# frontbreakoutSchematic.net
KiCad netlist of a schematic drawn in Altium Designer
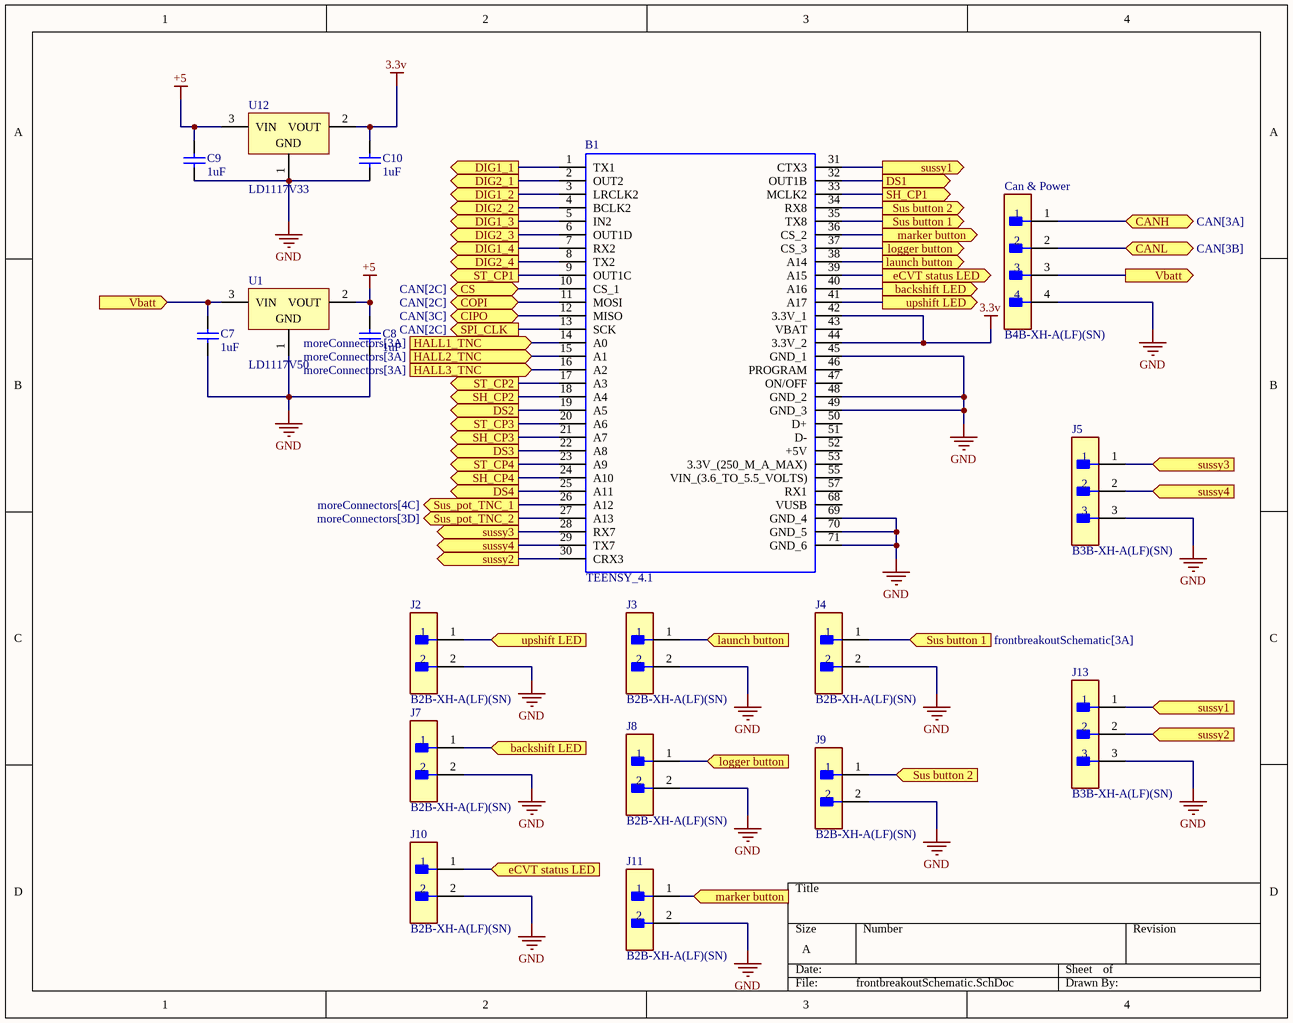
[diagram p0: frontbreakoutSchematic.SchDoc]

(export (version "E")
  (design (tool "Eeschema 10.0.6"))
  (components
    (comp (ref "B1")
      (value "TEENSY_4.1")
      (footprint "TEENSY41")
      (description "Teensy 4.1 Development Board")
      (fields (field (name "MANUFACTURER_PART_NUMBER") "TEENSY 4.1"))
      (libsource (lib "TEENSY_4.1") (part "TEENSY_4.1"))
    )
    (comp (ref "C7")
      (value "1uF")
      (footprint "CAPC2013X145X50LL20T25")
      (description "C0805C105K4PACTU")
      (fields (field (name "MANUFACTURER") "Kemet"))
      (libsource (lib "Altium Content Vault") (part "CAP"))
    )
    (comp (ref "C8")
      (value "1uF")
      (footprint "CAPC2013X145X50LL20T25")
      (description "C0805C105K4PACTU")
      (fields (field (name "MANUFACTURER") "Kemet"))
      (libsource (lib "Altium Content Vault") (part "CAP"))
    )
    (comp (ref "C9")
      (value "1uF")
      (footprint "CAPC2013X145X50LL20T25")
      (description "C0805C105K4PACTU")
      (fields (field (name "MANUFACTURER") "Kemet"))
      (libsource (lib "Altium Content Vault") (part "CAP"))
    )
    (comp (ref "C10")
      (value "1uF")
      (footprint "CAPC2013X145X50LL20T25")
      (description "C0805C105K4PACTU")
      (fields (field (name "MANUFACTURER") "Kemet"))
      (libsource (lib "Altium Content Vault") (part "CAP"))
    )
    (comp (ref "Can & Power")
      (value "B4B-XH-A(LF)(SN)")
      (footprint "FP-B4B-XH-A_LF_SN-MFG")
      (description "CONN HEADER VERT 4POS 2.5MM")
      (libsource (lib "Altium Content Vault") (part "299a8cea1bdcbc3624fe62c390fa72c"))
    )
    (comp (ref "J2")
      (value "B2B-XH-A(LF)(SN)")
      (footprint "FP-B2B-XH-A_LF_SN-MFG")
      (description "CONN HEADER VERT 2POS 2.5MM")
      (libsource (lib "Altium Content Vault") (part "3bc925449376181038e59eaffc5286c"))
    )
    (comp (ref "J3")
      (value "B2B-XH-A(LF)(SN)")
      (footprint "FP-B2B-XH-A_LF_SN-MFG")
      (description "CONN HEADER VERT 2POS 2.5MM")
      (libsource (lib "Altium Content Vault") (part "3bc925449376181038e59eaffc5286c"))
    )
    (comp (ref "J4")
      (value "B2B-XH-A(LF)(SN)")
      (footprint "FP-B2B-XH-A_LF_SN-MFG")
      (description "CONN HEADER VERT 2POS 2.5MM")
      (libsource (lib "Altium Content Vault") (part "3bc925449376181038e59eaffc5286c"))
    )
    (comp (ref "J5")
      (value "B3B-XH-A(LF)(SN)")
      (footprint "FP-B3B-XH-A_LF_SN-MFG")
      (description "CONN HEADER VERT 3POS 2.5MM")
      (libsource (lib "Altium Content Vault") (part "0d3f023dd272f625e17a2be33dea85f"))
    )
    (comp (ref "J7")
      (value "B2B-XH-A(LF)(SN)")
      (footprint "FP-B2B-XH-A_LF_SN-MFG")
      (description "CONN HEADER VERT 2POS 2.5MM")
      (libsource (lib "Altium Content Vault") (part "3bc925449376181038e59eaffc5286c"))
    )
    (comp (ref "J8")
      (value "B2B-XH-A(LF)(SN)")
      (footprint "FP-B2B-XH-A_LF_SN-MFG")
      (description "CONN HEADER VERT 2POS 2.5MM")
      (libsource (lib "Altium Content Vault") (part "3bc925449376181038e59eaffc5286c"))
    )
    (comp (ref "J9")
      (value "B2B-XH-A(LF)(SN)")
      (footprint "FP-B2B-XH-A_LF_SN-MFG")
      (description "CONN HEADER VERT 2POS 2.5MM")
      (libsource (lib "Altium Content Vault") (part "3bc925449376181038e59eaffc5286c"))
    )
    (comp (ref "J10")
      (value "B2B-XH-A(LF)(SN)")
      (footprint "FP-B2B-XH-A_LF_SN-MFG")
      (description "CONN HEADER VERT 2POS 2.5MM")
      (libsource (lib "Altium Content Vault") (part "3bc925449376181038e59eaffc5286c"))
    )
    (comp (ref "J11")
      (value "B2B-XH-A(LF)(SN)")
      (footprint "FP-B2B-XH-A_LF_SN-MFG")
      (description "CONN HEADER VERT 2POS 2.5MM")
      (libsource (lib "Altium Content Vault") (part "3bc925449376181038e59eaffc5286c"))
    )
    (comp (ref "J13")
      (value "B3B-XH-A(LF)(SN)")
      (footprint "FP-B3B-XH-A_LF_SN-MFG")
      (description "CONN HEADER VERT 3POS 2.5MM")
      (libsource (lib "Altium Content Vault") (part "0d3f023dd272f625e17a2be33dea85f"))
    )
    (comp (ref "U1")
      (value "LD1117V50")
      (footprint "TO220")
      (description "Fixed Low Drop Positive Voltage Regulator, 5V, 3-Pin TO-220")
      (libsource (lib "Altium Content Vault") (part "PM-REG-LD1117V-SIL3"))
    )
    (comp (ref "U12")
      (value "LD1117V33")
      (footprint "TO220")
      (description "Fixed Low Drop Positive Voltage Regulator, 3.3V, 3-Pin TO-220")
      (libsource (lib "Altium Content Vault") (part "PM-REG-LD1117V-SIL3"))
    )
  )
  (nets
    (net (code "1") (name "+5") (class "Default")
      (node (ref "C8") (pin "2") (pinfunction "2_2") (pintype "passive"))
      (node (ref "C9") (pin "2") (pinfunction "2_2") (pintype "passive"))
      (node (ref "U1") (pin "2") (pinfunction "VOUT_2") (pintype "power_in"))
      (node (ref "U12") (pin "3") (pinfunction "VIN_3") (pintype "power_in"))
    )
    (net (code "2") (name "/CANH") (class "Default")
      (node (ref "Can & Power") (pin "1") (pinfunction "1_1") (pintype "passive"))
    )
    (net (code "3") (name "/CANL") (class "Default")
      (node (ref "Can & Power") (pin "2") (pinfunction "2_2") (pintype "passive"))
    )
    (net (code "4") (name "/CIPO") (class "Default")
      (node (ref "B1") (pin "12") (pinfunction "MISO_12") (pintype "passive"))
    )
    (net (code "5") (name "/COPI") (class "Default")
      (node (ref "B1") (pin "11") (pinfunction "MOSI_11") (pintype "passive"))
    )
    (net (code "6") (name "/CS") (class "Default")
      (node (ref "B1") (pin "10") (pinfunction "CS_1_10") (pintype "passive"))
    )
    (net (code "7") (name "/DIG1_1") (class "Default")
      (node (ref "B1") (pin "1") (pinfunction "TX1_1") (pintype "passive"))
    )
    (net (code "8") (name "/DIG1_2") (class "Default")
      (node (ref "B1") (pin "3") (pinfunction "LRCLK2_3") (pintype "passive"))
    )
    (net (code "9") (name "/DIG1_3") (class "Default")
      (node (ref "B1") (pin "5") (pinfunction "IN2_5") (pintype "passive"))
    )
    (net (code "10") (name "/DIG1_4") (class "Default")
      (node (ref "B1") (pin "7") (pinfunction "RX2_7") (pintype "passive"))
    )
    (net (code "11") (name "/DIG2_1") (class "Default")
      (node (ref "B1") (pin "2") (pinfunction "OUT2_2") (pintype "passive"))
    )
    (net (code "12") (name "/DIG2_2") (class "Default")
      (node (ref "B1") (pin "4") (pinfunction "BCLK2_4") (pintype "passive"))
    )
    (net (code "13") (name "/DIG2_3") (class "Default")
      (node (ref "B1") (pin "6") (pinfunction "OUT1D_6") (pintype "passive"))
    )
    (net (code "14") (name "/DIG2_4") (class "Default")
      (node (ref "B1") (pin "8") (pinfunction "TX2_8") (pintype "passive"))
    )
    (net (code "15") (name "/DS1") (class "Default")
      (node (ref "B1") (pin "32") (pinfunction "OUT1B_32") (pintype "passive"))
    )
    (net (code "16") (name "/DS2") (class "Default")
      (node (ref "B1") (pin "19") (pinfunction "A5_19") (pintype "passive"))
    )
    (net (code "17") (name "/DS3") (class "Default")
      (node (ref "B1") (pin "22") (pinfunction "A8_22") (pintype "passive"))
    )
    (net (code "18") (name "/DS4") (class "Default")
      (node (ref "B1") (pin "25") (pinfunction "A11_25") (pintype "passive"))
    )
    (net (code "19") (name "/HALL1_TNC") (class "Default")
      (node (ref "B1") (pin "14") (pinfunction "A0_14") (pintype "passive"))
    )
    (net (code "20") (name "/HALL2_TNC") (class "Default")
      (node (ref "B1") (pin "15") (pinfunction "A1_15") (pintype "passive"))
    )
    (net (code "21") (name "/HALL3_TNC") (class "Default")
      (node (ref "B1") (pin "16") (pinfunction "A2_16") (pintype "passive"))
    )
    (net (code "22") (name "/SH_CP1") (class "Default")
      (node (ref "B1") (pin "33") (pinfunction "MCLK2_33") (pintype "passive"))
    )
    (net (code "23") (name "/SH_CP2") (class "Default")
      (node (ref "B1") (pin "18") (pinfunction "A4_18") (pintype "passive"))
    )
    (net (code "24") (name "/SH_CP3") (class "Default")
      (node (ref "B1") (pin "21") (pinfunction "A7_21") (pintype "passive"))
    )
    (net (code "25") (name "/SH_CP4") (class "Default")
      (node (ref "B1") (pin "24") (pinfunction "A10_24") (pintype "passive"))
    )
    (net (code "26") (name "/SPI_CLK") (class "Default")
      (node (ref "B1") (pin "13") (pinfunction "SCK_13") (pintype "passive"))
    )
    (net (code "27") (name "/ST_CP1") (class "Default")
      (node (ref "B1") (pin "9") (pinfunction "OUT1C_9") (pintype "passive"))
    )
    (net (code "28") (name "/ST_CP2") (class "Default")
      (node (ref "B1") (pin "17") (pinfunction "A3_17") (pintype "passive"))
    )
    (net (code "29") (name "/ST_CP3") (class "Default")
      (node (ref "B1") (pin "20") (pinfunction "A6_20") (pintype "passive"))
    )
    (net (code "30") (name "/ST_CP4") (class "Default")
      (node (ref "B1") (pin "23") (pinfunction "A9_23") (pintype "passive"))
    )
    (net (code "31") (name "/Sus button 1") (class "Default")
      (node (ref "B1") (pin "35") (pinfunction "TX8_35") (pintype "passive"))
      (node (ref "J4") (pin "1") (pinfunction "1_1") (pintype "passive"))
    )
    (net (code "32") (name "/Sus button 2") (class "Default")
      (node (ref "B1") (pin "34") (pinfunction "RX8_34") (pintype "passive"))
      (node (ref "J9") (pin "1") (pinfunction "1_1") (pintype "passive"))
    )
    (net (code "33") (name "/Sus_pot_TNC_1") (class "Default")
      (node (ref "B1") (pin "26") (pinfunction "A12_26") (pintype "passive"))
    )
    (net (code "34") (name "/Sus_pot_TNC_2") (class "Default")
      (node (ref "B1") (pin "27") (pinfunction "A13_27") (pintype "passive"))
    )
    (net (code "35") (name "/Vbatt") (class "Default")
      (node (ref "C7") (pin "2") (pinfunction "2_2") (pintype "passive"))
      (node (ref "Can & Power") (pin "3") (pinfunction "3_3") (pintype "passive"))
      (node (ref "U1") (pin "3") (pinfunction "VIN_3") (pintype "power_in"))
    )
    (net (code "36") (name "/backshift LED") (class "Default")
      (node (ref "B1") (pin "40") (pinfunction "A16_40") (pintype "passive"))
      (node (ref "J7") (pin "1") (pinfunction "1_1") (pintype "passive"))
    )
    (net (code "37") (name "/eCVT status LED") (class "Default")
      (node (ref "B1") (pin "39") (pinfunction "A15_39") (pintype "passive"))
      (node (ref "J10") (pin "1") (pinfunction "1_1") (pintype "passive"))
    )
    (net (code "38") (name "/launch button") (class "Default")
      (node (ref "B1") (pin "38") (pinfunction "A14_38") (pintype "passive"))
      (node (ref "J3") (pin "1") (pinfunction "1_1") (pintype "passive"))
    )
    (net (code "39") (name "/logger button") (class "Default")
      (node (ref "B1") (pin "37") (pinfunction "CS_3_37") (pintype "passive"))
      (node (ref "J8") (pin "1") (pinfunction "1_1") (pintype "passive"))
    )
    (net (code "40") (name "/marker button") (class "Default")
      (node (ref "B1") (pin "36") (pinfunction "CS_2_36") (pintype "passive"))
      (node (ref "J11") (pin "1") (pinfunction "1_1") (pintype "passive"))
    )
    (net (code "41") (name "/sussy1") (class "Default")
      (node (ref "B1") (pin "31") (pinfunction "CTX3_31") (pintype "passive"))
      (node (ref "J13") (pin "1") (pinfunction "1_1") (pintype "passive"))
    )
    (net (code "42") (name "/sussy2") (class "Default")
      (node (ref "B1") (pin "30") (pinfunction "CRX3_30") (pintype "passive"))
      (node (ref "J13") (pin "2") (pinfunction "2_2") (pintype "passive"))
    )
    (net (code "43") (name "/sussy3") (class "Default")
      (node (ref "B1") (pin "28") (pinfunction "RX7_28") (pintype "passive"))
      (node (ref "J5") (pin "1") (pinfunction "1_1") (pintype "passive"))
    )
    (net (code "44") (name "/sussy4") (class "Default")
      (node (ref "B1") (pin "29") (pinfunction "TX7_29") (pintype "passive"))
      (node (ref "J5") (pin "2") (pinfunction "2_2") (pintype "passive"))
    )
    (net (code "45") (name "/upshift LED") (class "Default")
      (node (ref "B1") (pin "41") (pinfunction "A17_41") (pintype "passive"))
      (node (ref "J2") (pin "1") (pinfunction "1_1") (pintype "passive"))
    )
    (net (code "46") (name "3.3v") (class "Default")
      (node (ref "B1") (pin "42") (pinfunction "3.3V_1_42") (pintype "passive"))
      (node (ref "B1") (pin "44") (pinfunction "3.3V_2_44") (pintype "passive"))
      (node (ref "C10") (pin "2") (pinfunction "2_2") (pintype "passive"))
      (node (ref "U12") (pin "2") (pinfunction "VOUT_2") (pintype "power_in"))
    )
    (net (code "47") (name "GND") (class "Default")
      (node (ref "B1") (pin "45") (pinfunction "GND_1_45") (pintype "passive"))
      (node (ref "B1") (pin "48") (pinfunction "GND_2_48") (pintype "passive"))
      (node (ref "B1") (pin "49") (pinfunction "GND_3_49") (pintype "passive"))
      (node (ref "B1") (pin "69") (pinfunction "GND_4_69") (pintype "passive"))
      (node (ref "B1") (pin "70") (pinfunction "GND_5_70") (pintype "passive"))
      (node (ref "B1") (pin "71") (pinfunction "GND_6_71") (pintype "passive"))
      (node (ref "C10") (pin "1") (pinfunction "1_1") (pintype "passive"))
      (node (ref "C7") (pin "1") (pinfunction "1_1") (pintype "passive"))
      (node (ref "C8") (pin "1") (pinfunction "1_1") (pintype "passive"))
      (node (ref "C9") (pin "1") (pinfunction "1_1") (pintype "passive"))
      (node (ref "Can & Power") (pin "4") (pinfunction "4_4") (pintype "passive"))
      (node (ref "J10") (pin "2") (pinfunction "2_2") (pintype "passive"))
      (node (ref "J11") (pin "2") (pinfunction "2_2") (pintype "passive"))
      (node (ref "J13") (pin "3") (pinfunction "3_3") (pintype "passive"))
      (node (ref "J2") (pin "2") (pinfunction "2_2") (pintype "passive"))
      (node (ref "J3") (pin "2") (pinfunction "2_2") (pintype "passive"))
      (node (ref "J4") (pin "2") (pinfunction "2_2") (pintype "passive"))
      (node (ref "J5") (pin "3") (pinfunction "3_3") (pintype "passive"))
      (node (ref "J7") (pin "2") (pinfunction "2_2") (pintype "passive"))
      (node (ref "J8") (pin "2") (pinfunction "2_2") (pintype "passive"))
      (node (ref "J9") (pin "2") (pinfunction "2_2") (pintype "passive"))
      (node (ref "U1") (pin "1") (pinfunction "GND_1") (pintype "power_in"))
      (node (ref "U12") (pin "1") (pinfunction "GND_1") (pintype "power_in"))
    )
    (net (code "48") (name "unconnected-(B1-+5V-Pad52)") (class "Default")
      (node (ref "B1") (pin "52") (pinfunction "+5V_52") (pintype "passive"))
    )
    (net (code "49") (name "unconnected-(B1-3.3V_(250_M_A_MAX)-Pad53)") (class "Default")
      (node (ref "B1") (pin "53") (pinfunction "3.3V_(250_M_A_MAX)_53") (pintype "passive"))
    )
    (net (code "50") (name "unconnected-(B1-D+-Pad50)") (class "Default")
      (node (ref "B1") (pin "50") (pinfunction "D+_50") (pintype "passive"))
    )
    (net (code "51") (name "unconnected-(B1-D--Pad51)") (class "Default")
      (node (ref "B1") (pin "51") (pinfunction "D-_51") (pintype "passive"))
    )
    (net (code "52") (name "unconnected-(B1-ON{slash}OFF-Pad47)") (class "Default")
      (node (ref "B1") (pin "47") (pinfunction "ON/OFF_47") (pintype "passive"))
    )
    (net (code "53") (name "unconnected-(B1-PROGRAM-Pad46)") (class "Default")
      (node (ref "B1") (pin "46") (pinfunction "PROGRAM_46") (pintype "passive"))
    )
    (net (code "54") (name "unconnected-(B1-RX1-Pad57)") (class "Default")
      (node (ref "B1") (pin "57") (pinfunction "RX1_57") (pintype "passive"))
    )
    (net (code "55") (name "unconnected-(B1-VBAT-Pad43)") (class "Default")
      (node (ref "B1") (pin "43") (pinfunction "VBAT_43") (pintype "passive"))
    )
    (net (code "56") (name "unconnected-(B1-VIN_(3.6_TO_5.5_VOLTS)-Pad55)") (class "Default")
      (node (ref "B1") (pin "55") (pinfunction "VIN_(3.6_TO_5.5_VOLTS)_55") (pintype "passive"))
    )
    (net (code "57") (name "unconnected-(B1-VUSB-Pad68)") (class "Default")
      (node (ref "B1") (pin "68") (pinfunction "VUSB_68") (pintype "passive"))
    )
  )
)
